# CentralBoard_less-smd.net
KiCad netlist of a schematic drawn in EAGLE
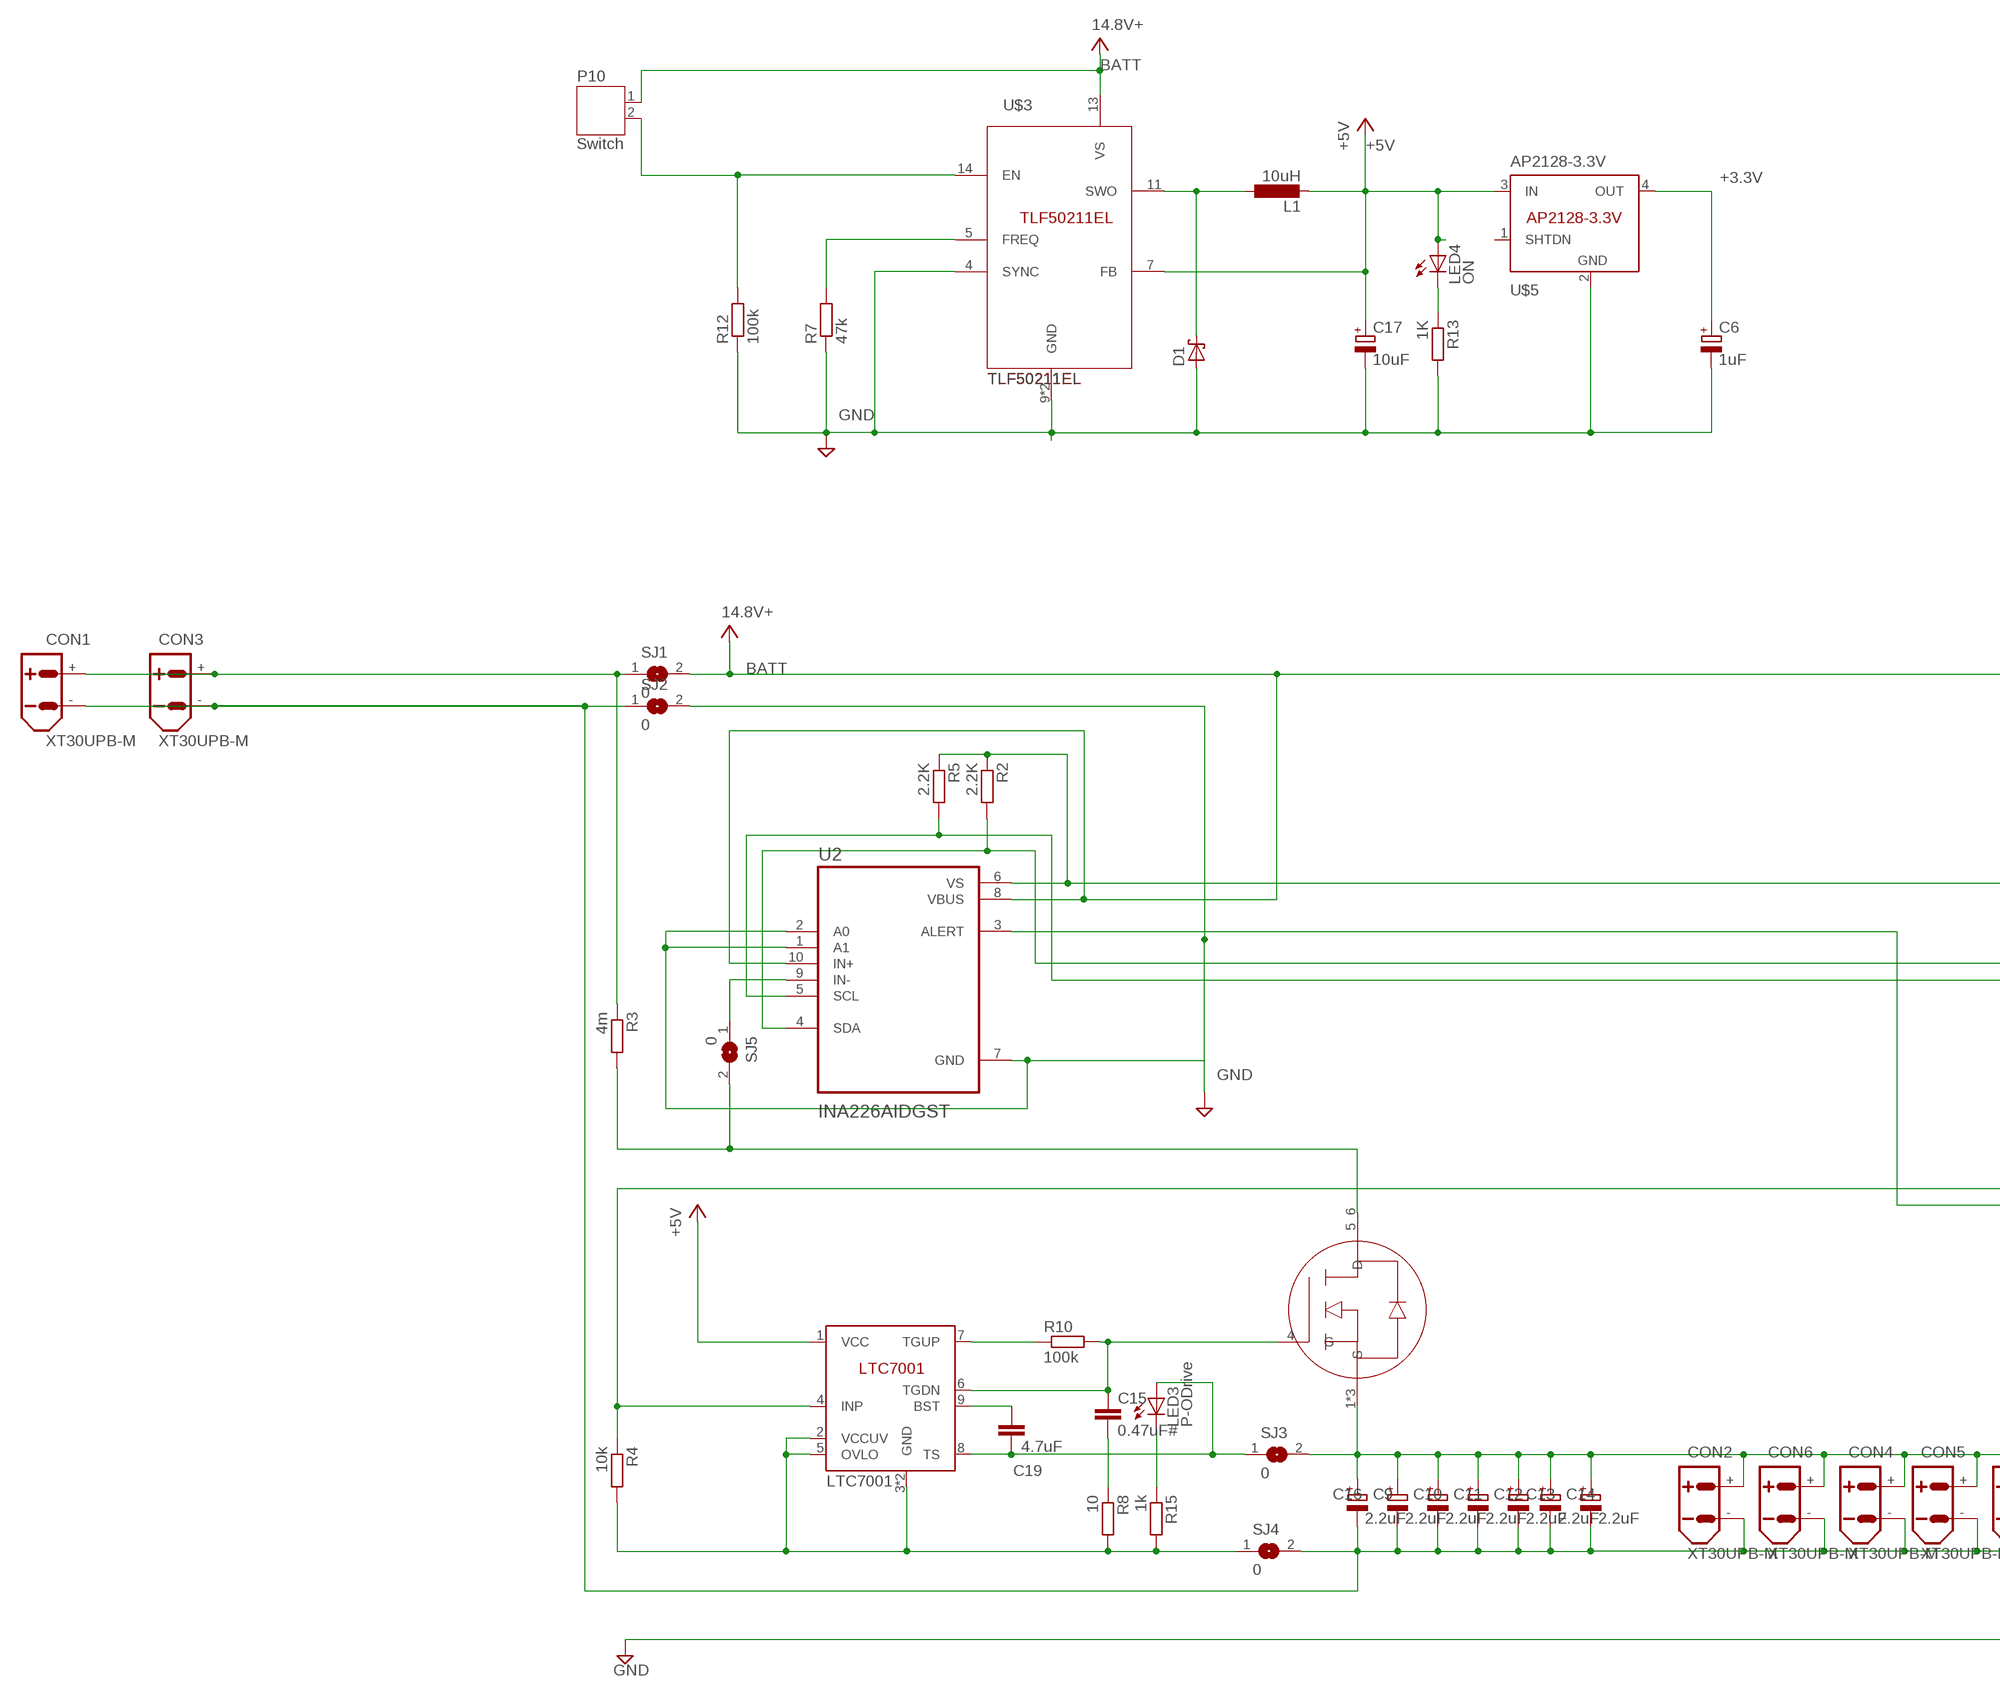
[diagram p0: schematic, sheet 1, part 1 of 2]
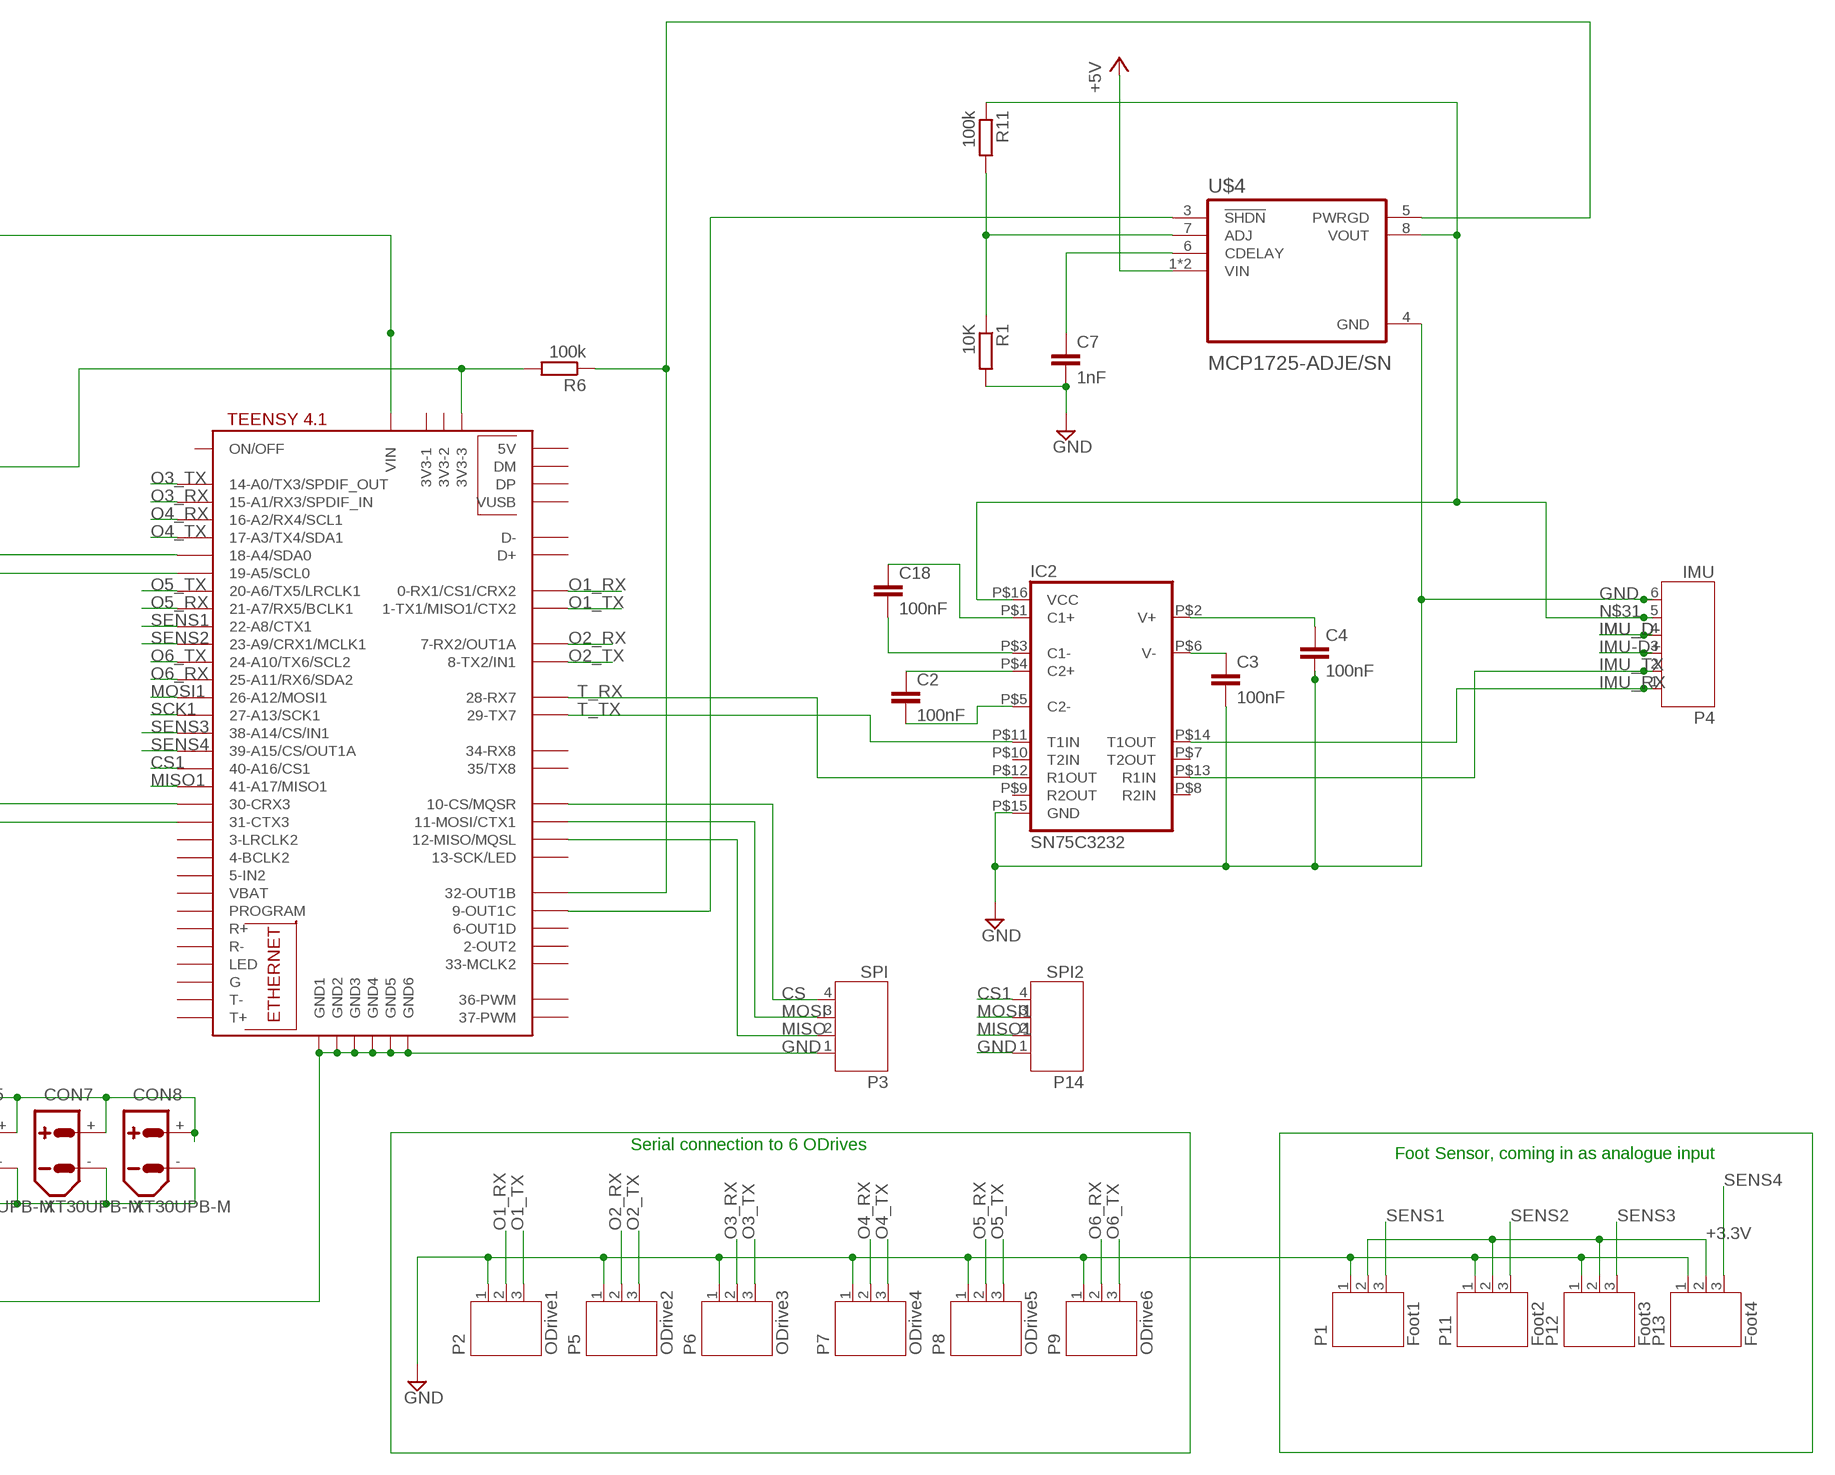
[diagram p1: schematic, sheet 1, part 2 of 2]

(export (version "E")
  (design (tool "Eeschema 10.0.6"))
  (components
    (comp (ref "C2")
      (value "100nF")
      (footprint "eagle-import:C025-025X050")
      (libsource (lib "eagle-import") (part "C-EU025-025X050"))
    )
    (comp (ref "C3")
      (value "100nF")
      (footprint "eagle-import:C025-025X050")
      (libsource (lib "eagle-import") (part "C-EU025-025X050"))
    )
    (comp (ref "C4")
      (value "100nF")
      (footprint "eagle-import:C025-025X050")
      (libsource (lib "eagle-import") (part "C-EU025-025X050"))
    )
    (comp (ref "C6")
      (value "1uF")
      (footprint "eagle-import:E2-4")
      (libsource (lib "eagle-import") (part "CPOL-EUE2-4"))
    )
    (comp (ref "C7")
      (value "1nF")
      (footprint "eagle-import:C025-025X050")
      (libsource (lib "eagle-import") (part "C-EU025-025X050"))
    )
    (comp (ref "C9")
      (value "2.2uF")
      (footprint "eagle-import:E2-5")
      (libsource (lib "eagle-import") (part "CPOL-EUE2-5"))
    )
    (comp (ref "C10")
      (value "2.2uF")
      (footprint "eagle-import:E2-5")
      (libsource (lib "eagle-import") (part "CPOL-EUE2-5"))
    )
    (comp (ref "C11")
      (value "2.2uF")
      (footprint "eagle-import:E2-5")
      (libsource (lib "eagle-import") (part "CPOL-EUE2-5"))
    )
    (comp (ref "C12")
      (value "2.2uF")
      (footprint "eagle-import:E2-5")
      (libsource (lib "eagle-import") (part "CPOL-EUE2-5"))
    )
    (comp (ref "C13")
      (value "2.2uF")
      (footprint "eagle-import:E2-5")
      (libsource (lib "eagle-import") (part "CPOL-EUE2-5"))
    )
    (comp (ref "C14")
      (value "2.2uF")
      (footprint "eagle-import:E2-5")
      (libsource (lib "eagle-import") (part "CPOL-EUE2-5"))
    )
    (comp (ref "C15")
      (value "0.47uF#")
      (footprint "eagle-import:C025-025X050")
      (libsource (lib "eagle-import") (part "C-EU025-025X050"))
    )
    (comp (ref "C16")
      (value "2.2uF")
      (footprint "eagle-import:E2-5")
      (libsource (lib "eagle-import") (part "CPOL-EUE2-5"))
    )
    (comp (ref "C17")
      (value "10uF")
      (footprint "eagle-import:E2-4")
      (libsource (lib "eagle-import") (part "CPOL-EUE2-4"))
    )
    (comp (ref "C18")
      (value "100nF")
      (footprint "eagle-import:C025-025X050")
      (libsource (lib "eagle-import") (part "C-EU025-025X050"))
    )
    (comp (ref "C19")
      (value "4.7uF")
      (footprint "eagle-import:C025-025X050")
      (libsource (lib "eagle-import") (part "C-EU025-025X050"))
    )
    (comp (ref "CON1")
      (value "XT30UPB-M")
      (footprint "eagle-import:XT30UPB-M")
      (libsource (lib "eagle-import") (part "XT30UPB-M"))
    )
    (comp (ref "CON2")
      (value "XT30UPB-M")
      (footprint "eagle-import:XT30UPB-M")
      (libsource (lib "eagle-import") (part "XT30UPB-M"))
    )
    (comp (ref "CON3")
      (value "XT30UPB-M")
      (footprint "eagle-import:XT30UPB-M")
      (libsource (lib "eagle-import") (part "XT30UPB-M"))
    )
    (comp (ref "CON4")
      (value "XT30UPB-M")
      (footprint "eagle-import:XT30UPB-M")
      (libsource (lib "eagle-import") (part "XT30UPB-M"))
    )
    (comp (ref "CON5")
      (value "XT30UPB-M")
      (footprint "eagle-import:XT30UPB-M")
      (libsource (lib "eagle-import") (part "XT30UPB-M"))
    )
    (comp (ref "CON6")
      (value "XT30UPB-M")
      (footprint "eagle-import:XT30UPB-M")
      (libsource (lib "eagle-import") (part "XT30UPB-M"))
    )
    (comp (ref "CON7")
      (value "XT30UPB-M")
      (footprint "eagle-import:XT30UPB-M")
      (libsource (lib "eagle-import") (part "XT30UPB-M"))
    )
    (comp (ref "CON8")
      (value "XT30UPB-M")
      (footprint "eagle-import:XT30UPB-M")
      (libsource (lib "eagle-import") (part "XT30UPB-M"))
    )
    (comp (ref "D1")
      (value "SCHOTTKY-DIODEDO41")
      (footprint "eagle-import:DO41-10")
      (libsource (lib "eagle-import") (part "SCHOTTKY-DIODEDO41"))
    )
    (comp (ref "IC2")
      (value "SN75C3232")
      (footprint "eagle-import:SOIC16")
      (fields (field (name "MF") "Maxim Integrated") (field (name "MP") "MAX3232"))
      (libsource (lib "eagle-import") (part "MAX3232"))
    )
    (comp (ref "IC3")
      (value "LTC7001")
      (footprint "eagle-import:MSOP10")
      (fields (field (name "MPN") "AD7992BRMZ-0"))
      (libsource (lib "eagle-import") (part "LTC7001"))
    )
    (comp (ref "L1")
      (value "10uH")
      (footprint "eagle-import:0204_5")
      (libsource (lib "eagle-import") (part "L-EU0204/5"))
    )
    (comp (ref "LED3")
      (value "P-ODrive")
      (footprint "eagle-import:LED3MM")
      (libsource (lib "eagle-import") (part "LED3MM"))
    )
    (comp (ref "LED4")
      (value "ON")
      (footprint "eagle-import:LED3MM")
      (libsource (lib "eagle-import") (part "LED3MM"))
    )
    (comp (ref "P1")
      (value "Foot1")
      (footprint "eagle-import:JST-PH3")
      (libsource (lib "eagle-import") (part "JST-PH3"))
    )
    (comp (ref "P2")
      (value "ODrive1")
      (footprint "eagle-import:JST-PH3")
      (libsource (lib "eagle-import") (part "JST-PH3"))
    )
    (comp (ref "P3")
      (value "SPI")
      (footprint "eagle-import:JST-PH4")
      (libsource (lib "eagle-import") (part "JST-PH4"))
    )
    (comp (ref "P4")
      (value "IMU")
      (footprint "eagle-import:JST-PH6")
      (libsource (lib "eagle-import") (part "JST-PH6"))
    )
    (comp (ref "P5")
      (value "ODrive2")
      (footprint "eagle-import:JST-PH3")
      (libsource (lib "eagle-import") (part "JST-PH3"))
    )
    (comp (ref "P6")
      (value "ODrive3")
      (footprint "eagle-import:JST-PH3")
      (libsource (lib "eagle-import") (part "JST-PH3"))
    )
    (comp (ref "P7")
      (value "ODrive4")
      (footprint "eagle-import:JST-PH3")
      (libsource (lib "eagle-import") (part "JST-PH3"))
    )
    (comp (ref "P8")
      (value "ODrive5")
      (footprint "eagle-import:JST-PH3")
      (libsource (lib "eagle-import") (part "JST-PH3"))
    )
    (comp (ref "P9")
      (value "ODrive6")
      (footprint "eagle-import:JST-PH3")
      (libsource (lib "eagle-import") (part "JST-PH3"))
    )
    (comp (ref "P10")
      (value "Switch")
      (footprint "eagle-import:JST-PH2")
      (libsource (lib "eagle-import") (part "JST-PH2"))
    )
    (comp (ref "P11")
      (value "Foot2")
      (footprint "eagle-import:JST-PH3")
      (libsource (lib "eagle-import") (part "JST-PH3"))
    )
    (comp (ref "P12")
      (value "Foot3")
      (footprint "eagle-import:JST-PH3")
      (libsource (lib "eagle-import") (part "JST-PH3"))
    )
    (comp (ref "P13")
      (value "Foot4")
      (footprint "eagle-import:JST-PH3")
      (libsource (lib "eagle-import") (part "JST-PH3"))
    )
    (comp (ref "P14")
      (value "SPI2")
      (footprint "eagle-import:JST-PH4")
      (libsource (lib "eagle-import") (part "JST-PH4"))
    )
    (comp (ref "R1")
      (value "10K")
      (footprint "eagle-import:0204_7")
      (libsource (lib "eagle-import") (part "R-EU_0204/7"))
    )
    (comp (ref "R2")
      (value "2.2K")
      (footprint "eagle-import:0204_7")
      (libsource (lib "eagle-import") (part "R-EU_0204/7"))
    )
    (comp (ref "R3")
      (value "4m")
      (footprint "eagle-import:R2512")
      (libsource (lib "eagle-import") (part "R-EU_R2512"))
    )
    (comp (ref "R4")
      (value "10k")
      (footprint "eagle-import:0204_7")
      (libsource (lib "eagle-import") (part "R-EU_0204/7"))
    )
    (comp (ref "R5")
      (value "2.2K")
      (footprint "eagle-import:0204_7")
      (libsource (lib "eagle-import") (part "R-EU_0204/7"))
    )
    (comp (ref "R6")
      (value "100k")
      (footprint "eagle-import:0204_7")
      (libsource (lib "eagle-import") (part "R-EU_0204/7"))
    )
    (comp (ref "R7")
      (value "47k")
      (footprint "eagle-import:0204_7")
      (libsource (lib "eagle-import") (part "R-EU_0204/7"))
    )
    (comp (ref "R8")
      (value "10")
      (footprint "eagle-import:0204_7")
      (libsource (lib "eagle-import") (part "R-EU_0204/7"))
    )
    (comp (ref "R10")
      (value "100k")
      (footprint "eagle-import:0204_7")
      (libsource (lib "eagle-import") (part "R-EU_0204/7"))
    )
    (comp (ref "R11")
      (value "100k")
      (footprint "eagle-import:0204_7")
      (libsource (lib "eagle-import") (part "R-EU_0204/7"))
    )
    (comp (ref "R12")
      (value "100k")
      (footprint "eagle-import:0204_7")
      (libsource (lib "eagle-import") (part "R-EU_0204/7"))
    )
    (comp (ref "R13")
      (value "1K")
      (footprint "eagle-import:0204_7")
      (libsource (lib "eagle-import") (part "R-EU_0204/7"))
    )
    (comp (ref "R15")
      (value "1k")
      (footprint "eagle-import:0204_7")
      (libsource (lib "eagle-import") (part "R-EU_0204/7"))
    )
    (comp (ref "SJ1") (value "0") (footprint "eagle-import:SJ") (libsource (lib "eagle-import") (part "SJ")))
    (comp (ref "SJ2") (value "0") (footprint "eagle-import:SJ") (libsource (lib "eagle-import") (part "SJ")))
    (comp (ref "SJ3") (value "0") (footprint "eagle-import:SJ") (libsource (lib "eagle-import") (part "SJ")))
    (comp (ref "SJ4") (value "0") (footprint "eagle-import:SJ") (libsource (lib "eagle-import") (part "SJ")))
    (comp (ref "SJ5") (value "0") (footprint "eagle-import:SJ") (libsource (lib "eagle-import") (part "SJ")))
    (comp (ref "U$1")
      (value "TEENSY41")
      (footprint "eagle-import:TEENSY41")
      (libsource (lib "eagle-import") (part "TEENSY41"))
    )
    (comp (ref "U$2")
      (value "DMTH8003SPS")
      (footprint "eagle-import:DIO_NTS1045EMFST1G")
      (libsource (lib "eagle-import") (part "NVMFS6H824NL-D"))
    )
    (comp (ref "U$3")
      (value "TLF50211EL")
      (footprint "eagle-import:TSSOP-14")
      (libsource (lib "eagle-import") (part "TLF50211EL"))
    )
    (comp (ref "U$4")
      (value "MCP1725-ADJE/SN")
      (footprint "eagle-import:SOIC127P599X175-8N")
      (fields (field (name "MF") "Microchip"))
      (libsource (lib "eagle-import") (part "MCP1725-ADJE/SN"))
    )
    (comp (ref "U$5")
      (value "AP2128-3.3V")
      (footprint "eagle-import:SOT-23-5")
      (libsource (lib "eagle-import") (part "AP2128-3.3V"))
    )
    (comp (ref "U2")
      (value "INA226AIDGST")
      (footprint "eagle-import:SOP50P490X110-10N")
      (fields (field (name "MF") "Texas Instruments"))
      (libsource (lib "eagle-import") (part "INA226AIDGST"))
    )
  )
  (nets
    (net (code "1") (name "+5V") (class "Default")
      (node (ref "C17") (pin "+") (pinfunction "+_+") (pintype "passive"))
      (node (ref "IC3") (pin "1") (pinfunction "VCC_1") (pintype "power_in"))
      (node (ref "L1") (pin "2") (pinfunction "2_2") (pintype "passive"))
      (node (ref "LED4") (pin "A") (pinfunction "A_A") (pintype "passive"))
      (node (ref "U$3") (pin "7") (pinfunction "FB_7") (pintype "bidirectional"))
      (node (ref "U$4") (pin "1") (pinfunction "VIN_1") (pintype "input"))
      (node (ref "U$4") (pin "2") (pinfunction "VIN_2") (pintype "input"))
      (node (ref "U$5") (pin "3") (pinfunction "IN_3") (pintype "input"))
    )
    (net (code "2") (name "/+3.3V") (class "Default")
      (node (ref "C6") (pin "+") (pinfunction "+_+") (pintype "passive"))
      (node (ref "P1") (pin "2") (pinfunction "2_2") (pintype "passive"))
      (node (ref "P11") (pin "2") (pinfunction "2_2") (pintype "passive"))
      (node (ref "P12") (pin "2") (pinfunction "2_2") (pintype "passive"))
      (node (ref "P13") (pin "2") (pinfunction "2_2") (pintype "passive"))
      (node (ref "U$5") (pin "4") (pinfunction "OUT_4") (pintype "output"))
    )
    (net (code "3") (name "/CS") (class "Default")
      (node (ref "P3") (pin "4") (pinfunction "4_4") (pintype "passive"))
      (node (ref "U$1") (pin "10-CS\\MQSR") (pinfunction "10-CS/MQSR_10-CS\\MQSR") (pintype "bidirectional"))
    )
    (net (code "4") (name "/CS1") (class "Default")
      (node (ref "P14") (pin "4") (pinfunction "4_4") (pintype "passive"))
      (node (ref "U$1") (pin "40-A16/CS1") (pinfunction "40-A16/CS1_40-A16/CS1") (pintype "bidirectional"))
    )
    (net (code "5") (name "/IMU-D+") (class "Default")
      (node (ref "P4") (pin "3") (pinfunction "3_3") (pintype "passive"))
    )
    (net (code "6") (name "/IMU_D-") (class "Default")
      (node (ref "P4") (pin "4") (pinfunction "4_4") (pintype "passive"))
    )
    (net (code "7") (name "/IMU_RX") (class "Default")
      (node (ref "IC2") (pin "P$14") (pinfunction "T1OUT_P$14") (pintype "output"))
      (node (ref "P4") (pin "1") (pinfunction "1_1") (pintype "passive"))
    )
    (net (code "8") (name "/IMU_TX") (class "Default")
      (node (ref "IC2") (pin "P$13") (pinfunction "R1IN_P$13") (pintype "input"))
      (node (ref "P4") (pin "2") (pinfunction "2_2") (pintype "passive"))
    )
    (net (code "9") (name "/MISO") (class "Default")
      (node (ref "P3") (pin "2") (pinfunction "2_2") (pintype "passive"))
      (node (ref "U$1") (pin "12-MISO/MQSL") (pinfunction "12-MISO/MQSL_12-MISO/MQSL") (pintype "bidirectional"))
    )
    (net (code "10") (name "/MISO1") (class "Default")
      (node (ref "P14") (pin "2") (pinfunction "2_2") (pintype "passive"))
      (node (ref "U$1") (pin "41-A17/MISO1") (pinfunction "41-A17/MISO1_41-A17/MISO1") (pintype "bidirectional"))
    )
    (net (code "11") (name "/MOSI") (class "Default")
      (node (ref "P3") (pin "3") (pinfunction "3_3") (pintype "passive"))
      (node (ref "U$1") (pin "11-MOSI/CTX1") (pinfunction "11-MOSI/CTX1_11-MOSI/CTX1") (pintype "bidirectional"))
    )
    (net (code "12") (name "/MOSI1") (class "Default")
      (node (ref "P14") (pin "3") (pinfunction "3_3") (pintype "passive"))
      (node (ref "U$1") (pin "26-A12/MOSI1") (pinfunction "26-A12/MOSI1_26-A12/MOSI1") (pintype "bidirectional"))
    )
    (net (code "13") (name "/N$31") (class "Default")
      (node (ref "IC2") (pin "P$16") (pinfunction "VCC_P$16") (pintype "power_in"))
      (node (ref "P4") (pin "5") (pinfunction "5_5") (pintype "passive"))
      (node (ref "R11") (pin "1") (pinfunction "1_1") (pintype "passive"))
      (node (ref "U$4") (pin "8") (pinfunction "VOUT_8") (pintype "output"))
    )
    (net (code "14") (name "/O1_RX") (class "Default")
      (node (ref "P2") (pin "2") (pinfunction "2_2") (pintype "passive"))
      (node (ref "U$1") (pin "0-RX1/CS1/CRX2") (pinfunction "0-RX1/CS1/CRX2_0-RX1/CS1/CRX2") (pintype "bidirectional"))
    )
    (net (code "15") (name "/O1_TX") (class "Default")
      (node (ref "P2") (pin "3") (pinfunction "3_3") (pintype "passive"))
      (node (ref "U$1") (pin "1-TX1/MISO1/CTX2") (pinfunction "1-TX1/MISO1/CTX2_1-TX1/MISO1/CTX2") (pintype "bidirectional"))
    )
    (net (code "16") (name "/O2_RX") (class "Default")
      (node (ref "P5") (pin "2") (pinfunction "2_2") (pintype "passive"))
      (node (ref "U$1") (pin "7-RX2/OUT1A") (pinfunction "7-RX2/OUT1A_7-RX2/OUT1A") (pintype "bidirectional"))
    )
    (net (code "17") (name "/O2_TX") (class "Default")
      (node (ref "P5") (pin "3") (pinfunction "3_3") (pintype "passive"))
      (node (ref "U$1") (pin "8-TX2/IN1") (pinfunction "8-TX2/IN1_8-TX2/IN1") (pintype "bidirectional"))
    )
    (net (code "18") (name "/O3_RX") (class "Default")
      (node (ref "P6") (pin "2") (pinfunction "2_2") (pintype "passive"))
      (node (ref "U$1") (pin "15-A1/RX3/SPDIF_IN") (pinfunction "15-A1/RX3/SPDIF_IN_15-A1/RX3/SPDIF_IN") (pintype "bidirectional"))
    )
    (net (code "19") (name "/O3_TX") (class "Default")
      (node (ref "P6") (pin "3") (pinfunction "3_3") (pintype "passive"))
      (node (ref "U$1") (pin "14-A0/TX3/SPDIF_OUT") (pinfunction "14-A0/TX3/SPDIF_OUT_14-A0/TX3/SPDIF_OUT") (pintype "bidirectional"))
    )
    (net (code "20") (name "/O4_RX") (class "Default")
      (node (ref "P7") (pin "2") (pinfunction "2_2") (pintype "passive"))
      (node (ref "U$1") (pin "16-A2/RX4/SCL1") (pinfunction "16-A2/RX4/SCL1_16-A2/RX4/SCL1") (pintype "bidirectional"))
    )
    (net (code "21") (name "/O4_TX") (class "Default")
      (node (ref "P7") (pin "3") (pinfunction "3_3") (pintype "passive"))
      (node (ref "U$1") (pin "17-A3/TX4/SDA1") (pinfunction "17-A3/TX4/SDA1_17-A3/TX4/SDA1") (pintype "bidirectional"))
    )
    (net (code "22") (name "/O5_RX") (class "Default")
      (node (ref "P8") (pin "2") (pinfunction "2_2") (pintype "passive"))
      (node (ref "U$1") (pin "21-A7/RX5/BCLK1") (pinfunction "21-A7/RX5/BCLK1_21-A7/RX5/BCLK1") (pintype "bidirectional"))
    )
    (net (code "23") (name "/O5_TX") (class "Default")
      (node (ref "P8") (pin "3") (pinfunction "3_3") (pintype "passive"))
      (node (ref "U$1") (pin "20-A6/TX5/LRCLK1") (pinfunction "20-A6/TX5/LRCLK1_20-A6/TX5/LRCLK1") (pintype "bidirectional"))
    )
    (net (code "24") (name "/O6_RX") (class "Default")
      (node (ref "P9") (pin "2") (pinfunction "2_2") (pintype "passive"))
      (node (ref "U$1") (pin "25-A11/RX6/SDA2") (pinfunction "25-A11/RX6/SDA2_25-A11/RX6/SDA2") (pintype "bidirectional"))
    )
    (net (code "25") (name "/O6_TX") (class "Default")
      (node (ref "P9") (pin "3") (pinfunction "3_3") (pintype "passive"))
      (node (ref "U$1") (pin "24-A10/TX6/SCL2") (pinfunction "24-A10/TX6/SCL2_24-A10/TX6/SCL2") (pintype "bidirectional"))
    )
    (net (code "26") (name "/SCK1") (class "Default")
      (node (ref "U$1") (pin "27-A13/SCK1") (pinfunction "27-A13/SCK1_27-A13/SCK1") (pintype "bidirectional"))
    )
    (net (code "27") (name "/SENS1") (class "Default")
      (node (ref "P1") (pin "3") (pinfunction "3_3") (pintype "passive"))
      (node (ref "U$1") (pin "22-A8/CTX1") (pinfunction "22-A8/CTX1_22-A8/CTX1") (pintype "bidirectional"))
    )
    (net (code "28") (name "/SENS2") (class "Default")
      (node (ref "P11") (pin "3") (pinfunction "3_3") (pintype "passive"))
      (node (ref "U$1") (pin "23-A9/CRX1/MCLK1") (pinfunction "23-A9/CRX1/MCLK1_23-A9/CRX1/MCLK1") (pintype "bidirectional"))
    )
    (net (code "29") (name "/SENS3") (class "Default")
      (node (ref "P12") (pin "3") (pinfunction "3_3") (pintype "passive"))
      (node (ref "U$1") (pin "38-A14/CS/IN1") (pinfunction "38-A14/CS/IN1_38-A14/CS/IN1") (pintype "bidirectional"))
    )
    (net (code "30") (name "/SENS4") (class "Default")
      (node (ref "P13") (pin "3") (pinfunction "3_3") (pintype "passive"))
      (node (ref "U$1") (pin "39-A15/CS/OUT1A") (pinfunction "39-A15/CS/OUT1A_39-A15/CS/OUT1A") (pintype "bidirectional"))
    )
    (net (code "31") (name "/T_RX") (class "Default")
      (node (ref "IC2") (pin "P$12") (pinfunction "R1OUT_P$12") (pintype "output"))
      (node (ref "U$1") (pin "28-RX7") (pinfunction "28-RX7_28-RX7") (pintype "bidirectional"))
    )
    (net (code "32") (name "/T_TX") (class "Default")
      (node (ref "IC2") (pin "P$11") (pinfunction "T1IN_P$11") (pintype "input"))
      (node (ref "U$1") (pin "29-TX7") (pinfunction "29-TX7_29-TX7") (pintype "bidirectional"))
    )
    (net (code "33") (name "14.8V+") (class "Default")
      (node (ref "P10") (pin "1") (pinfunction "1_1") (pintype "passive"))
      (node (ref "SJ1") (pin "2") (pinfunction "2_2") (pintype "passive"))
      (node (ref "U$3") (pin "13") (pinfunction "VS_13") (pintype "bidirectional"))
      (node (ref "U2") (pin "10") (pinfunction "IN+_10") (pintype "input"))
      (node (ref "U2") (pin "8") (pinfunction "VBUS_8") (pintype "power_in"))
    )
    (net (code "34") (name "GND") (class "Default")
      (node (ref "C17") (pin "-") (pinfunction "-_-") (pintype "passive"))
      (node (ref "C3") (pin "2") (pinfunction "2_2") (pintype "passive"))
      (node (ref "C4") (pin "2") (pinfunction "2_2") (pintype "passive"))
      (node (ref "C6") (pin "-") (pinfunction "-_-") (pintype "passive"))
      (node (ref "C7") (pin "2") (pinfunction "2_2") (pintype "passive"))
      (node (ref "D1") (pin "A") (pinfunction "A_A") (pintype "passive"))
      (node (ref "IC2") (pin "P$15") (pinfunction "GND_P$15") (pintype "power_in"))
      (node (ref "P1") (pin "1") (pinfunction "1_1") (pintype "passive"))
      (node (ref "P11") (pin "1") (pinfunction "1_1") (pintype "passive"))
      (node (ref "P12") (pin "1") (pinfunction "1_1") (pintype "passive"))
      (node (ref "P13") (pin "1") (pinfunction "1_1") (pintype "passive"))
      (node (ref "P14") (pin "1") (pinfunction "1_1") (pintype "passive"))
      (node (ref "P2") (pin "1") (pinfunction "1_1") (pintype "passive"))
      (node (ref "P3") (pin "1") (pinfunction "1_1") (pintype "passive"))
      (node (ref "P4") (pin "6") (pinfunction "6_6") (pintype "passive"))
      (node (ref "P5") (pin "1") (pinfunction "1_1") (pintype "passive"))
      (node (ref "P6") (pin "1") (pinfunction "1_1") (pintype "passive"))
      (node (ref "P7") (pin "1") (pinfunction "1_1") (pintype "passive"))
      (node (ref "P8") (pin "1") (pinfunction "1_1") (pintype "passive"))
      (node (ref "P9") (pin "1") (pinfunction "1_1") (pintype "passive"))
      (node (ref "R1") (pin "2") (pinfunction "2_2") (pintype "passive"))
      (node (ref "R12") (pin "1") (pinfunction "1_1") (pintype "passive"))
      (node (ref "R13") (pin "2") (pinfunction "2_2") (pintype "passive"))
      (node (ref "R7") (pin "1") (pinfunction "1_1") (pintype "passive"))
      (node (ref "SJ2") (pin "2") (pinfunction "2_2") (pintype "passive"))
      (node (ref "U$1") (pin "GND1") (pinfunction "GND1_GND1") (pintype "bidirectional"))
      (node (ref "U$1") (pin "GND2") (pinfunction "GND2_GND2") (pintype "bidirectional"))
      (node (ref "U$1") (pin "GND3") (pinfunction "GND3_GND3") (pintype "bidirectional"))
      (node (ref "U$1") (pin "GND4") (pinfunction "GND4_GND4") (pintype "bidirectional"))
      (node (ref "U$1") (pin "GND5") (pinfunction "GND5_GND5") (pintype "bidirectional"))
      (node (ref "U$1") (pin "GND6") (pinfunction "GND6_GND6") (pintype "bidirectional"))
      (node (ref "U$3") (pin "10") (pinfunction "GND_10") (pintype "bidirectional"))
      (node (ref "U$3") (pin "4") (pinfunction "SYNC_4") (pintype "bidirectional"))
      (node (ref "U$3") (pin "9") (pinfunction "GND_9") (pintype "bidirectional"))
      (node (ref "U$4") (pin "4") (pinfunction "GND_4") (pintype "power_in"))
      (node (ref "U$5") (pin "2") (pinfunction "GND_2") (pintype "power_in"))
      (node (ref "U2") (pin "1") (pinfunction "A1_1") (pintype "input"))
      (node (ref "U2") (pin "2") (pinfunction "A0_2") (pintype "input"))
      (node (ref "U2") (pin "7") (pinfunction "GND_7") (pintype "power_in"))
    )
    (net (code "35") (name "Net-(C10-Pad+)") (class "Default")
      (node (ref "C10") (pin "+") (pinfunction "+_+") (pintype "passive"))
      (node (ref "C11") (pin "+") (pinfunction "+_+") (pintype "passive"))
      (node (ref "C12") (pin "+") (pinfunction "+_+") (pintype "passive"))
      (node (ref "C13") (pin "+") (pinfunction "+_+") (pintype "passive"))
      (node (ref "C14") (pin "+") (pinfunction "+_+") (pintype "passive"))
      (node (ref "C16") (pin "+") (pinfunction "+_+") (pintype "passive"))
      (node (ref "C9") (pin "+") (pinfunction "+_+") (pintype "passive"))
      (node (ref "CON2") (pin "+") (pinfunction "+_+") (pintype "power_in"))
      (node (ref "CON4") (pin "+") (pinfunction "+_+") (pintype "power_in"))
      (node (ref "CON5") (pin "+") (pinfunction "+_+") (pintype "power_in"))
      (node (ref "CON6") (pin "+") (pinfunction "+_+") (pintype "power_in"))
      (node (ref "CON7") (pin "+") (pinfunction "+_+") (pintype "power_in"))
      (node (ref "CON8") (pin "+") (pinfunction "+_+") (pintype "power_in"))
      (node (ref "SJ3") (pin "2") (pinfunction "2_2") (pintype "passive"))
      (node (ref "U$2") (pin "1") (pinfunction "S_1") (pintype "bidirectional"))
      (node (ref "U$2") (pin "2") (pinfunction "S_2") (pintype "bidirectional"))
      (node (ref "U$2") (pin "3") (pinfunction "S_3") (pintype "bidirectional"))
    )
    (net (code "36") (name "Net-(C10-Pad-)") (class "Default")
      (node (ref "C10") (pin "-") (pinfunction "-_-") (pintype "passive"))
      (node (ref "C11") (pin "-") (pinfunction "-_-") (pintype "passive"))
      (node (ref "C12") (pin "-") (pinfunction "-_-") (pintype "passive"))
      (node (ref "C13") (pin "-") (pinfunction "-_-") (pintype "passive"))
      (node (ref "C14") (pin "-") (pinfunction "-_-") (pintype "passive"))
      (node (ref "C16") (pin "-") (pinfunction "-_-") (pintype "passive"))
      (node (ref "C9") (pin "-") (pinfunction "-_-") (pintype "passive"))
      (node (ref "CON1") (pin "-") (pinfunction "-_-") (pintype "power_in"))
      (node (ref "CON2") (pin "-") (pinfunction "-_-") (pintype "power_in"))
      (node (ref "CON3") (pin "-") (pinfunction "-_-") (pintype "power_in"))
      (node (ref "CON4") (pin "-") (pinfunction "-_-") (pintype "power_in"))
      (node (ref "CON5") (pin "-") (pinfunction "-_-") (pintype "power_in"))
      (node (ref "CON6") (pin "-") (pinfunction "-_-") (pintype "power_in"))
      (node (ref "CON7") (pin "-") (pinfunction "-_-") (pintype "power_in"))
      (node (ref "CON8") (pin "-") (pinfunction "-_-") (pintype "power_in"))
      (node (ref "SJ2") (pin "1") (pinfunction "1_1") (pintype "passive"))
      (node (ref "SJ4") (pin "2") (pinfunction "2_2") (pintype "passive"))
    )
    (net (code "37") (name "Net-(C15-Pad2)") (class "Default")
      (node (ref "C15") (pin "2") (pinfunction "2_2") (pintype "passive"))
      (node (ref "R8") (pin "1") (pinfunction "1_1") (pintype "passive"))
    )
    (net (code "38") (name "Net-(CON1-Pad+)") (class "Default")
      (node (ref "CON1") (pin "+") (pinfunction "+_+") (pintype "power_in"))
      (node (ref "CON3") (pin "+") (pinfunction "+_+") (pintype "power_in"))
      (node (ref "R3") (pin "1") (pinfunction "1_1") (pintype "passive"))
      (node (ref "SJ1") (pin "1") (pinfunction "1_1") (pintype "passive"))
    )
    (net (code "39") (name "Net-(IC2-C1+)") (class "Default")
      (node (ref "C18") (pin "1") (pinfunction "1_1") (pintype "passive"))
      (node (ref "IC2") (pin "P$1") (pinfunction "C1+_P$1") (pintype "passive"))
    )
    (net (code "40") (name "Net-(IC2-C1-)") (class "Default")
      (node (ref "C18") (pin "2") (pinfunction "2_2") (pintype "passive"))
      (node (ref "IC2") (pin "P$3") (pinfunction "C1-_P$3") (pintype "passive"))
    )
    (net (code "41") (name "Net-(IC2-C2+)") (class "Default")
      (node (ref "C2") (pin "1") (pinfunction "1_1") (pintype "passive"))
      (node (ref "IC2") (pin "P$4") (pinfunction "C2+_P$4") (pintype "passive"))
    )
    (net (code "42") (name "Net-(IC2-C2-)") (class "Default")
      (node (ref "C2") (pin "2") (pinfunction "2_2") (pintype "passive"))
      (node (ref "IC2") (pin "P$5") (pinfunction "C2-_P$5") (pintype "passive"))
    )
    (net (code "43") (name "Net-(IC2-V+)") (class "Default")
      (node (ref "C4") (pin "1") (pinfunction "1_1") (pintype "passive"))
      (node (ref "IC2") (pin "P$2") (pinfunction "V+_P$2") (pintype "passive"))
    )
    (net (code "44") (name "Net-(IC2-V-)") (class "Default")
      (node (ref "C3") (pin "1") (pinfunction "1_1") (pintype "passive"))
      (node (ref "IC2") (pin "P$6") (pinfunction "V-_P$6") (pintype "passive"))
    )
    (net (code "45") (name "Net-(IC3-BST)") (class "Default")
      (node (ref "C19") (pin "1") (pinfunction "1_1") (pintype "passive"))
      (node (ref "IC3") (pin "9") (pinfunction "BST_9") (pintype "input"))
    )
    (net (code "46") (name "Net-(IC3-INP)") (class "Default")
      (node (ref "IC3") (pin "4") (pinfunction "INP_4") (pintype "input"))
      (node (ref "R4") (pin "1") (pinfunction "1_1") (pintype "passive"))
      (node (ref "U$1") (pin "30-CRX3") (pinfunction "30-CRX3_30-CRX3") (pintype "bidirectional"))
    )
    (net (code "47") (name "Net-(IC3-OVLO)") (class "Default")
      (node (ref "IC3") (pin "11") (pinfunction "GND_11") (pintype "power_in"))
      (node (ref "IC3") (pin "2") (pinfunction "VCCUV_2") (pintype "input"))
      (node (ref "IC3") (pin "3") (pinfunction "GND_3") (pintype "power_in"))
      (node (ref "IC3") (pin "5") (pinfunction "OVLO_5") (pintype "power_in"))
      (node (ref "R15") (pin "2") (pinfunction "2_2") (pintype "passive"))
      (node (ref "R4") (pin "2") (pinfunction "2_2") (pintype "passive"))
      (node (ref "R8") (pin "2") (pinfunction "2_2") (pintype "passive"))
      (node (ref "SJ4") (pin "1") (pinfunction "1_1") (pintype "passive"))
    )
    (net (code "48") (name "Net-(IC3-TGDN)") (class "Default")
      (node (ref "C15") (pin "1") (pinfunction "1_1") (pintype "passive"))
      (node (ref "IC3") (pin "6") (pinfunction "TGDN_6") (pintype "output"))
      (node (ref "R10") (pin "2") (pinfunction "2_2") (pintype "passive"))
      (node (ref "U$2") (pin "4") (pinfunction "G_4") (pintype "bidirectional"))
    )
    (net (code "49") (name "Net-(IC3-TGUP)") (class "Default")
      (node (ref "IC3") (pin "7") (pinfunction "TGUP_7") (pintype "input"))
      (node (ref "R10") (pin "1") (pinfunction "1_1") (pintype "passive"))
    )
    (net (code "50") (name "Net-(IC3-TS)") (class "Default")
      (node (ref "C19") (pin "2") (pinfunction "2_2") (pintype "passive"))
      (node (ref "IC3") (pin "8") (pinfunction "TS_8") (pintype "bidirectional"))
      (node (ref "LED3") (pin "A") (pinfunction "A_A") (pintype "passive"))
      (node (ref "SJ3") (pin "1") (pinfunction "1_1") (pintype "passive"))
    )
    (net (code "51") (name "Net-(LED3-C)") (class "Default")
      (node (ref "LED3") (pin "K") (pinfunction "C_K") (pintype "passive"))
      (node (ref "R15") (pin "1") (pinfunction "1_1") (pintype "passive"))
    )
    (net (code "52") (name "Net-(LED4-C)") (class "Default")
      (node (ref "LED4") (pin "K") (pinfunction "C_K") (pintype "passive"))
      (node (ref "R13") (pin "1") (pinfunction "1_1") (pintype "passive"))
    )
    (net (code "53") (name "Net-(U$2-D)") (class "Default")
      (node (ref "R3") (pin "2") (pinfunction "2_2") (pintype "passive"))
      (node (ref "SJ5") (pin "2") (pinfunction "2_2") (pintype "passive"))
      (node (ref "U$2") (pin "5_6") (pinfunction "D_5_6") (pintype "bidirectional"))
    )
    (net (code "54") (name "Net-(U$3-EN)") (class "Default")
      (node (ref "P10") (pin "2") (pinfunction "2_2") (pintype "passive"))
      (node (ref "R12") (pin "2") (pinfunction "2_2") (pintype "passive"))
      (node (ref "U$3") (pin "14") (pinfunction "EN_14") (pintype "bidirectional"))
    )
    (net (code "55") (name "Net-(U$3-FREQ)") (class "Default")
      (node (ref "R7") (pin "2") (pinfunction "2_2") (pintype "passive"))
      (node (ref "U$3") (pin "5") (pinfunction "FREQ_5") (pintype "bidirectional"))
    )
    (net (code "56") (name "Net-(U$3-SWO)") (class "Default")
      (node (ref "D1") (pin "C") (pinfunction "C_C") (pintype "passive"))
      (node (ref "L1") (pin "1") (pinfunction "1_1") (pintype "passive"))
      (node (ref "U$3") (pin "11") (pinfunction "SWO_11") (pintype "bidirectional"))
    )
    (net (code "57") (name "Net-(U$4-ADJ)") (class "Default")
      (node (ref "R1") (pin "1") (pinfunction "1_1") (pintype "passive"))
      (node (ref "R11") (pin "2") (pinfunction "2_2") (pintype "passive"))
      (node (ref "U$4") (pin "7") (pinfunction "ADJ_7") (pintype "input"))
    )
    (net (code "58") (name "Net-(U$4-CDELAY)") (class "Default")
      (node (ref "C7") (pin "1") (pinfunction "1_1") (pintype "passive"))
      (node (ref "U$4") (pin "6") (pinfunction "CDELAY_6") (pintype "input"))
    )
    (net (code "59") (name "Net-(U$4-PWRGD)") (class "Default")
      (node (ref "R6") (pin "1") (pinfunction "1_1") (pintype "passive"))
      (node (ref "U$1") (pin "32-OUT1B") (pinfunction "32-OUT1B_32-OUT1B") (pintype "bidirectional"))
      (node (ref "U$4") (pin "5") (pinfunction "PWRGD_5") (pintype "output"))
    )
    (net (code "60") (name "Net-(U$4-~{SHDN})") (class "Default")
      (node (ref "U$1") (pin "9-OUT1C") (pinfunction "9-OUT1C_9-OUT1C") (pintype "bidirectional"))
      (node (ref "U$4") (pin "3") (pinfunction "~{SHDN}_3") (pintype "input"))
    )
    (net (code "61") (name "Net-(U2-ALERT)") (class "Default")
      (node (ref "U$1") (pin "31-CTX3") (pinfunction "31-CTX3_31-CTX3") (pintype "bidirectional"))
      (node (ref "U2") (pin "3") (pinfunction "ALERT_3") (pintype "output"))
    )
    (net (code "62") (name "Net-(U2-IN-)") (class "Default")
      (node (ref "SJ5") (pin "1") (pinfunction "1_1") (pintype "passive"))
      (node (ref "U2") (pin "9") (pinfunction "IN-_9") (pintype "input"))
    )
    (net (code "63") (name "Net-(U2-SCL)") (class "Default")
      (node (ref "R5") (pin "2") (pinfunction "2_2") (pintype "passive"))
      (node (ref "U$1") (pin "19-A5/SCL0") (pinfunction "19-A5/SCL0_19-A5/SCL0") (pintype "bidirectional"))
      (node (ref "U2") (pin "5") (pinfunction "SCL_5") (pintype "input"))
    )
    (net (code "64") (name "Net-(U2-SDA)") (class "Default")
      (node (ref "R2") (pin "2") (pinfunction "2_2") (pintype "passive"))
      (node (ref "U$1") (pin "18-A4/SDA0") (pinfunction "18-A4/SDA0_18-A4/SDA0") (pintype "bidirectional"))
      (node (ref "U2") (pin "4") (pinfunction "SDA_4") (pintype "bidirectional"))
    )
    (net (code "65") (name "Net-(U2-VS)") (class "Default")
      (node (ref "R2") (pin "1") (pinfunction "1_1") (pintype "passive"))
      (node (ref "R5") (pin "1") (pinfunction "1_1") (pintype "passive"))
      (node (ref "R6") (pin "2") (pinfunction "2_2") (pintype "passive"))
      (node (ref "U$1") (pin "3V3-3") (pinfunction "3V3-3_3V3-3") (pintype "bidirectional"))
      (node (ref "U2") (pin "6") (pinfunction "VS_6") (pintype "power_in"))
    )
    (net (code "66") (name "unconnected-(IC2-R2IN-PadP$8)") (class "Default")
      (node (ref "IC2") (pin "P$8") (pinfunction "R2IN_P$8") (pintype "input"))
    )
    (net (code "67") (name "unconnected-(IC2-R2OUT-PadP$9)") (class "Default")
      (node (ref "IC2") (pin "P$9") (pinfunction "R2OUT_P$9") (pintype "output"))
    )
    (net (code "68") (name "unconnected-(IC2-T2IN-PadP$10)") (class "Default")
      (node (ref "IC2") (pin "P$10") (pinfunction "T2IN_P$10") (pintype "input"))
    )
    (net (code "69") (name "unconnected-(IC2-T2OUT-PadP$7)") (class "Default")
      (node (ref "IC2") (pin "P$7") (pinfunction "T2OUT_P$7") (pintype "output"))
    )
    (net (code "70") (name "unconnected-(U$1-5V-Pad+5V)") (class "Default")
      (node (ref "U$1") (pin "+5V") (pinfunction "5V_+5V") (pintype "bidirectional"))
    )
    (net (code "71") (name "unconnected-(U$1-35{slash}TX8-Pad35-TX8)") (class "Default")
      (node (ref "U$1") (pin "35-TX8") (pinfunction "35/TX8_35-TX8") (pintype "bidirectional"))
    )
    (net (code "72") (name "unconnected-(U$1-Pad2-OUT2)") (class "Default")
      (node (ref "U$1") (pin "2-OUT2") (pinfunction "2-OUT2_2-OUT2") (pintype "bidirectional"))
    )
    (net (code "73") (name "unconnected-(U$1-Pad3-LRCLK2)") (class "Default")
      (node (ref "U$1") (pin "3-LRCLK2") (pinfunction "3-LRCLK2_3-LRCLK2") (pintype "bidirectional"))
    )
    (net (code "74") (name "unconnected-(U$1-Pad3V3-1)") (class "Default")
      (node (ref "U$1") (pin "3V3-1") (pinfunction "3V3-1_3V3-1") (pintype "bidirectional"))
    )
    (net (code "75") (name "unconnected-(U$1-Pad3V3-2)") (class "Default")
      (node (ref "U$1") (pin "3V3-2") (pinfunction "3V3-2_3V3-2") (pintype "bidirectional"))
    )
    (net (code "76") (name "unconnected-(U$1-Pad4-BCLK2)") (class "Default")
      (node (ref "U$1") (pin "4-BCLK2") (pinfunction "4-BCLK2_4-BCLK2") (pintype "bidirectional"))
    )
    (net (code "77") (name "unconnected-(U$1-Pad5-IN2)") (class "Default")
      (node (ref "U$1") (pin "5-IN2") (pinfunction "5-IN2_5-IN2") (pintype "bidirectional"))
    )
    (net (code "78") (name "unconnected-(U$1-Pad6-OUT1D)") (class "Default")
      (node (ref "U$1") (pin "6-OUT1D") (pinfunction "6-OUT1D_6-OUT1D") (pintype "bidirectional"))
    )
    (net (code "79") (name "unconnected-(U$1-Pad13-SCK{slash}LED)") (class "Default")
      (node (ref "U$1") (pin "13-SCK/LED") (pinfunction "13-SCK/LED_13-SCK/LED") (pintype "bidirectional"))
    )
    (net (code "80") (name "unconnected-(U$1-Pad33-MCLK2)") (class "Default")
      (node (ref "U$1") (pin "33-MCLK2") (pinfunction "33-MCLK2_33-MCLK2") (pintype "bidirectional"))
    )
    (net (code "81") (name "unconnected-(U$1-Pad34-RX8)") (class "Default")
      (node (ref "U$1") (pin "34-RX8") (pinfunction "34-RX8_34-RX8") (pintype "bidirectional"))
    )
    (net (code "82") (name "unconnected-(U$1-Pad36-PWM)") (class "Default")
      (node (ref "U$1") (pin "36-PWM") (pinfunction "36-PWM_36-PWM") (pintype "bidirectional"))
    )
    (net (code "83") (name "unconnected-(U$1-Pad37-PWM)") (class "Default")
      (node (ref "U$1") (pin "37-PWM") (pinfunction "37-PWM_37-PWM") (pintype "bidirectional"))
    )
    (net (code "84") (name "unconnected-(U$1-PadD+)") (class "Default")
      (node (ref "U$1") (pin "D+") (pinfunction "D+_D+") (pintype "bidirectional"))
    )
    (net (code "85") (name "unconnected-(U$1-PadD-)") (class "Default")
      (node (ref "U$1") (pin "D-") (pinfunction "D-_D-") (pintype "bidirectional"))
    )
    (net (code "86") (name "unconnected-(U$1-PadDM)") (class "Default")
      (node (ref "U$1") (pin "DM") (pinfunction "DM_DM") (pintype "bidirectional"))
    )
    (net (code "87") (name "unconnected-(U$1-PadDP)") (class "Default")
      (node (ref "U$1") (pin "DP") (pinfunction "DP_DP") (pintype "bidirectional"))
    )
    (net (code "88") (name "unconnected-(U$1-PadG)") (class "Default")
      (node (ref "U$1") (pin "G") (pinfunction "G_G") (pintype "bidirectional"))
    )
    (net (code "89") (name "unconnected-(U$1-PadLED)") (class "Default")
      (node (ref "U$1") (pin "LED") (pinfunction "LED_LED") (pintype "bidirectional"))
    )
    (net (code "90") (name "unconnected-(U$1-PadON{slash}OFF)") (class "Default")
      (node (ref "U$1") (pin "ON/OFF") (pinfunction "ON/OFF_ON/OFF") (pintype "bidirectional"))
    )
    (net (code "91") (name "unconnected-(U$1-PadPROGRAM)") (class "Default")
      (node (ref "U$1") (pin "PROGRAM") (pinfunction "PROGRAM_PROGRAM") (pintype "bidirectional"))
    )
    (net (code "92") (name "unconnected-(U$1-PadR+)") (class "Default")
      (node (ref "U$1") (pin "R+") (pinfunction "R+_R+") (pintype "bidirectional"))
    )
    (net (code "93") (name "unconnected-(U$1-PadR-)") (class "Default")
      (node (ref "U$1") (pin "R-") (pinfunction "R-_R-") (pintype "bidirectional"))
    )
    (net (code "94") (name "unconnected-(U$1-PadT+)") (class "Default")
      (node (ref "U$1") (pin "T+") (pinfunction "T+_T+") (pintype "bidirectional"))
    )
    (net (code "95") (name "unconnected-(U$1-PadT-)") (class "Default")
      (node (ref "U$1") (pin "T-") (pinfunction "T-_T-") (pintype "bidirectional"))
    )
    (net (code "96") (name "unconnected-(U$1-PadVBAT)") (class "Default")
      (node (ref "U$1") (pin "VBAT") (pinfunction "VBAT_VBAT") (pintype "bidirectional"))
    )
    (net (code "97") (name "unconnected-(U$1-PadVIN)") (class "Default")
      (node (ref "U$1") (pin "VIN") (pinfunction "VIN_VIN") (pintype "bidirectional"))
    )
    (net (code "98") (name "unconnected-(U$1-PadVUSB)") (class "Default")
      (node (ref "U$1") (pin "VUSB") (pinfunction "VUSB_VUSB") (pintype "bidirectional"))
    )
    (net (code "99") (name "unconnected-(U$5-SHTDN-Pad1)") (class "Default")
      (node (ref "U$5") (pin "1") (pinfunction "SHTDN_1") (pintype "bidirectional"))
    )
  )
)
